# cc2652rb_v3.net
KiCad netlist of a schematic drawn in EAGLE
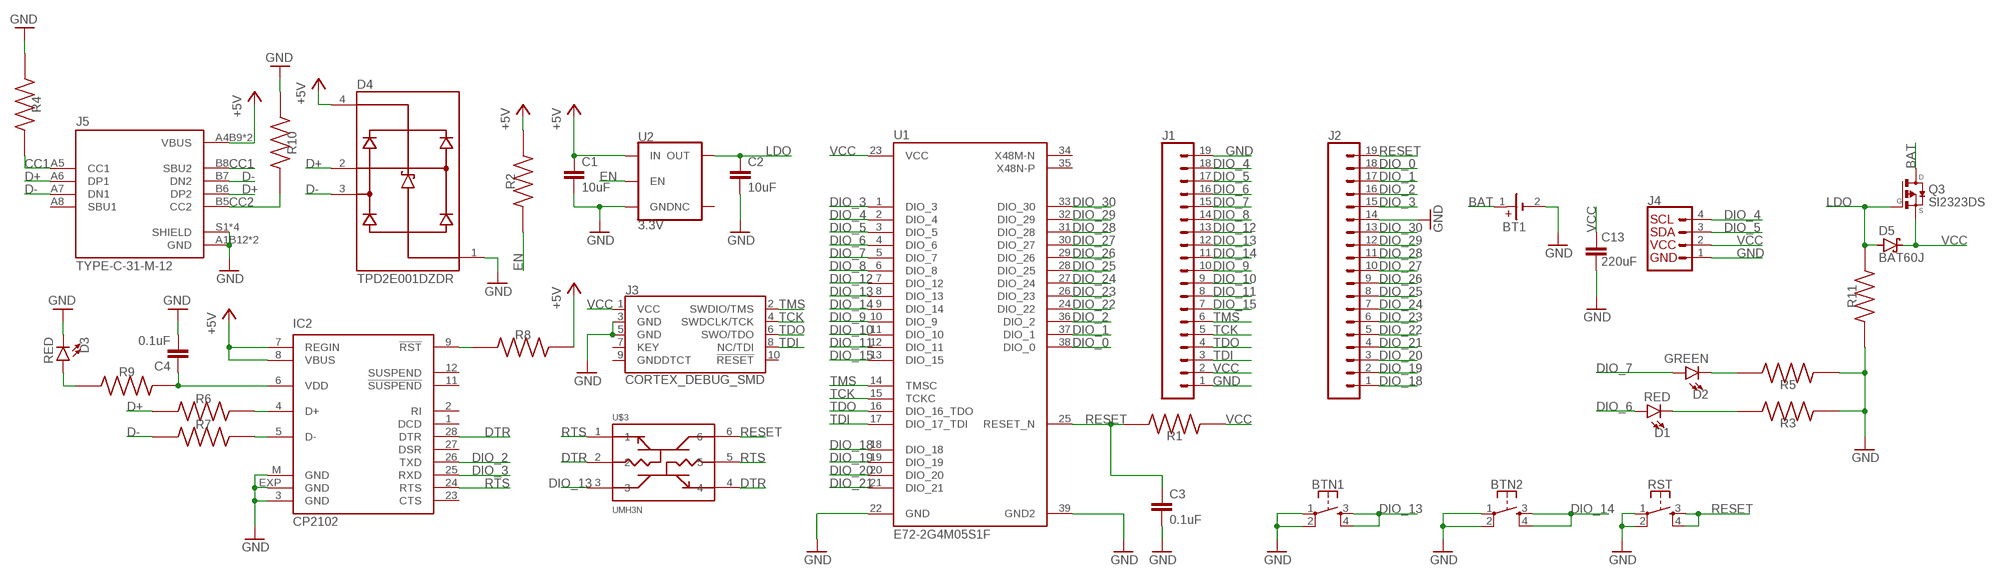
[diagram p0: schematic, sheet 1]

(export (version "E")
  (design (tool "Eeschema 10.0.6"))
  (components
    (comp (ref "BT1")
      (value "79527141")
      (footprint "eagle-import:79527141")
      (fields
        (field (name "DIGIKEY_PART_NO") "732-12325-2-ND")
        (field (name "MANUFACTURER") "Wurth Electronics Inc.")
        (field (name "CREATED_BY") "PCBLayout.com")
      )
      (libsource (lib "eagle-import") (part "79527141"))
    )
    (comp (ref "BTN1")
      (value "MOMENTARY-SWITCH-SPST-2-SMD-4.6X2.8MM")
      (footprint "eagle-import:TACTILE_SWITCH_SMD_4.6X2.8MM")
      (libsource (lib "eagle-import") (part "MOMENTARY-SWITCH-SPST-2-SMD-4.6X2.8MM"))
    )
    (comp (ref "BTN2")
      (value "MOMENTARY-SWITCH-SPST-2-SMD-4.6X2.8MM")
      (footprint "eagle-import:TACTILE_SWITCH_SMD_4.6X2.8MM")
      (libsource (lib "eagle-import") (part "MOMENTARY-SWITCH-SPST-2-SMD-4.6X2.8MM"))
    )
    (comp (ref "C1")
      (value "10uF")
      (footprint "eagle-import:0603")
      (libsource (lib "eagle-import") (part "10UF-0603-6.3V-20%"))
    )
    (comp (ref "C2")
      (value "10uF")
      (footprint "eagle-import:0603")
      (libsource (lib "eagle-import") (part "10UF-0603-6.3V-20%"))
    )
    (comp (ref "C3")
      (value "0.1uF")
      (footprint "eagle-import:0603")
      (libsource (lib "eagle-import") (part "0.1UF-0603-25V-(+80/-20%)"))
    )
    (comp (ref "C4")
      (value "0.1uF")
      (footprint "eagle-import:0603")
      (libsource (lib "eagle-import") (part "0.1UF-0603-25V-(+80/-20%)"))
    )
    (comp (ref "C13")
      (value "220uF")
      (footprint "eagle-import:CAPM7343X310")
      (libsource (lib "eagle-import") (part "CTANTALUM-2917(7343-METRIC)_"))
    )
    (comp (ref "D1")
      (value "RED")
      (footprint "eagle-import:LED-0603")
      (libsource (lib "eagle-import") (part "LED-RED0603"))
    )
    (comp (ref "D2")
      (value "GREEN")
      (footprint "eagle-import:LED-0603")
      (libsource (lib "eagle-import") (part "LED-GREEN0603"))
    )
    (comp (ref "D3")
      (value "RED")
      (footprint "eagle-import:LED-0603")
      (libsource (lib "eagle-import") (part "LED-RED0603"))
    )
    (comp (ref "D4")
      (value "TPD2E001DZDR")
      (footprint "eagle-import:SOT192P237X122-4N")
      (fields (field (name "MF") "Texas Instruments"))
      (libsource (lib "eagle-import") (part "TPD2E001DZDR"))
    )
    (comp (ref "D5")
      (value "BAT60J")
      (footprint "eagle-import:SOD323_ST")
      (libsource (lib "eagle-import") (part "BAT60J"))
    )
    (comp (ref "IC2")
      (value "CP2102")
      (footprint "eagle-import:MLP28")
      (fields (field (name "MF") "FARNELL") (field (name "MPN") "CP2102-GM"))
      (libsource (lib "eagle-import") (part "CP2102"))
    )
    (comp (ref "J1")
      (value "CONN_191X19_NO_SILK")
      (footprint "eagle-import:1X19_NO_SILK")
      (libsource (lib "eagle-import") (part "CONN_191X19_NO_SILK"))
    )
    (comp (ref "J2")
      (value "CONN_191X19_NO_SILK")
      (footprint "eagle-import:1X19_NO_SILK")
      (libsource (lib "eagle-import") (part "CONN_191X19_NO_SILK"))
    )
    (comp (ref "J3")
      (value "CORTEX_DEBUG_SMD")
      (footprint "eagle-import:SAMTECH_FTSH-105-01")
      (libsource (lib "eagle-import") (part "CORTEX_DEBUG_SMD"))
    )
    (comp (ref "J4")
      (value "QWIIC_CONNECTORJS-1MM")
      (footprint "eagle-import:1X04_1MM_RA")
      (libsource (lib "eagle-import") (part "QWIIC_CONNECTORJS-1MM"))
    )
    (comp (ref "J5")
      (value "TYPE-C-31-M-12")
      (footprint "eagle-import:HRO_TYPE-C-31-M-12")
      (fields (field (name "MF") "HRO Electronics Co., Ltd."))
      (libsource (lib "eagle-import") (part "TYPE-C-31-M-12"))
    )
    (comp (ref "Q3")
      (value "SI2323DS")
      (footprint "eagle-import:SOT23")
      (fields (field (name "MF") "Vishay Siliconix"))
      (libsource (lib "eagle-import") (part "SI2323DS"))
    )
    (comp (ref "R1")
      (value "100k")
      (footprint "eagle-import:RESC1005X40N")
      (fields (field (name "MF") "Yageo") (field (name "MP") "RC0402FR-073M6L"))
      (libsource (lib "eagle-import") (part "RC0402FR-073M6L"))
    )
    (comp (ref "R2")
      (value "10k")
      (footprint "eagle-import:RESC1005X40N")
      (fields (field (name "MF") "Yageo") (field (name "MP") "RC0402FR-073M6L"))
      (libsource (lib "eagle-import") (part "RC0402FR-073M6L"))
    )
    (comp (ref "R3")
      (value "2k")
      (footprint "eagle-import:RESC1005X40N")
      (fields (field (name "MF") "Yageo") (field (name "MP") "RC0402FR-073M6L"))
      (libsource (lib "eagle-import") (part "RC0402FR-073M6L"))
    )
    (comp (ref "R4")
      (value "5.1k")
      (footprint "eagle-import:RESC1005X40N")
      (fields (field (name "MF") "Yageo") (field (name "MP") "RC0402FR-073M6L"))
      (libsource (lib "eagle-import") (part "RC0402FR-073M6L"))
    )
    (comp (ref "R5")
      (value "2k")
      (footprint "eagle-import:RESC1005X40N")
      (fields (field (name "MF") "Yageo") (field (name "MP") "RC0402FR-073M6L"))
      (libsource (lib "eagle-import") (part "RC0402FR-073M6L"))
    )
    (comp (ref "R6")
      (value "33Ohm")
      (footprint "eagle-import:RESC1005X40N")
      (fields (field (name "MF") "Yageo") (field (name "MP") "RC0402FR-073M6L"))
      (libsource (lib "eagle-import") (part "RC0402FR-073M6L"))
    )
    (comp (ref "R7")
      (value "33Ohm")
      (footprint "eagle-import:RESC1005X40N")
      (fields (field (name "MF") "Yageo") (field (name "MP") "RC0402FR-073M6L"))
      (libsource (lib "eagle-import") (part "RC0402FR-073M6L"))
    )
    (comp (ref "R8")
      (value "10k")
      (footprint "eagle-import:RESC1005X40N")
      (fields (field (name "MF") "Yageo") (field (name "MP") "RC0402FR-073M6L"))
      (libsource (lib "eagle-import") (part "RC0402FR-073M6L"))
    )
    (comp (ref "R9")
      (value "RC0402FR-073M6L")
      (footprint "eagle-import:RESC1005X40N")
      (fields (field (name "MF") "Yageo"))
      (libsource (lib "eagle-import") (part "RC0402FR-073M6L"))
    )
    (comp (ref "R10")
      (value "5.1k")
      (footprint "eagle-import:RESC1005X40N")
      (fields (field (name "MF") "Yageo") (field (name "MP") "RC0402FR-073M6L"))
      (libsource (lib "eagle-import") (part "RC0402FR-073M6L"))
    )
    (comp (ref "R11")
      (value "10k")
      (footprint "eagle-import:RESC1005X40N")
      (fields (field (name "MF") "Yageo") (field (name "MP") "RC0402FR-073M6L"))
      (libsource (lib "eagle-import") (part "RC0402FR-073M6L"))
    )
    (comp (ref "RST")
      (value "MOMENTARY-SWITCH-SPST-2-SMD-4.6X2.8MM")
      (footprint "eagle-import:TACTILE_SWITCH_SMD_4.6X2.8MM")
      (libsource (lib "eagle-import") (part "MOMENTARY-SWITCH-SPST-2-SMD-4.6X2.8MM"))
    )
    (comp (ref "U$3")
      (value "UMH3N")
      (footprint "eagle-import:SOP65P210X100-6N")
      (fields (field (name "MF") "Rohm"))
      (libsource (lib "eagle-import") (part "UMH3N"))
    )
    (comp (ref "U1")
      (value "E72-2G4M05S1F")
      (footprint "eagle-import:E72-2G4M05S1F")
      (libsource (lib "eagle-import") (part "E72-2G4M05S1F"))
    )
    (comp (ref "U2")
      (value "3.3V")
      (footprint "eagle-import:SOT23-5")
      (libsource (lib "eagle-import") (part "V_REG_AP2112K-3.3V"))
    )
  )
  (nets
    (net (code "1") (name "+5V") (class "Default")
      (node (ref "C1") (pin "1") (pinfunction "1_1") (pintype "passive"))
      (node (ref "D4") (pin "4") (pinfunction "VCC_4") (pintype "power_in"))
      (node (ref "IC2") (pin "7") (pinfunction "REGIN_7") (pintype "passive"))
      (node (ref "IC2") (pin "8") (pinfunction "VBUS_8") (pintype "input"))
      (node (ref "J5") (pin "A4B9") (pinfunction "VBUS_A4B9") (pintype "power_in"))
      (node (ref "J5") (pin "B4A9") (pinfunction "VBUS_B4A9") (pintype "power_in"))
      (node (ref "R2") (pin "2") (pinfunction "2_2") (pintype "passive"))
      (node (ref "R8") (pin "2") (pinfunction "2_2") (pintype "passive"))
      (node (ref "U2") (pin "1") (pinfunction "IN_1") (pintype "input"))
    )
    (net (code "2") (name "/BAT") (class "Default")
      (node (ref "BT1") (pin "1") (pinfunction "+_1") (pintype "passive"))
      (node (ref "Q3") (pin "3") (pinfunction "D_3") (pintype "passive"))
    )
    (net (code "3") (name "/CC1") (class "Default")
      (node (ref "J5") (pin "A5") (pinfunction "CC1_A5") (pintype "bidirectional"))
      (node (ref "J5") (pin "B8") (pinfunction "SBU2_B8") (pintype "bidirectional"))
      (node (ref "R4") (pin "2") (pinfunction "2_2") (pintype "passive"))
    )
    (net (code "4") (name "/CC2") (class "Default")
      (node (ref "J5") (pin "B5") (pinfunction "CC2_B5") (pintype "bidirectional"))
      (node (ref "R10") (pin "2") (pinfunction "2_2") (pintype "passive"))
    )
    (net (code "5") (name "/D+") (class "Default")
      (node (ref "D4") (pin "2") (pinfunction "IO1_2") (pintype "bidirectional"))
      (node (ref "J5") (pin "A6") (pinfunction "DP1_A6") (pintype "bidirectional"))
      (node (ref "J5") (pin "B6") (pinfunction "DP2_B6") (pintype "bidirectional"))
      (node (ref "R6") (pin "1") (pinfunction "1_1") (pintype "passive"))
    )
    (net (code "6") (name "/D-") (class "Default")
      (node (ref "D4") (pin "3") (pinfunction "IO2_3") (pintype "bidirectional"))
      (node (ref "J5") (pin "A7") (pinfunction "DN1_A7") (pintype "bidirectional"))
      (node (ref "J5") (pin "B7") (pinfunction "DN2_B7") (pintype "bidirectional"))
      (node (ref "R7") (pin "1") (pinfunction "1_1") (pintype "passive"))
    )
    (net (code "7") (name "/DIO_0") (class "Default")
      (node (ref "J2") (pin "18") (pinfunction "18_18") (pintype "passive"))
      (node (ref "U1") (pin "38") (pinfunction "DIO_0_38") (pintype "bidirectional"))
    )
    (net (code "8") (name "/DIO_1") (class "Default")
      (node (ref "J2") (pin "17") (pinfunction "17_17") (pintype "passive"))
      (node (ref "U1") (pin "37") (pinfunction "DIO_1_37") (pintype "bidirectional"))
    )
    (net (code "9") (name "/DIO_2") (class "Default")
      (node (ref "IC2") (pin "26") (pinfunction "TXD_26") (pintype "output"))
      (node (ref "J2") (pin "16") (pinfunction "16_16") (pintype "passive"))
      (node (ref "U1") (pin "36") (pinfunction "DIO_2_36") (pintype "bidirectional"))
    )
    (net (code "10") (name "/DIO_3") (class "Default")
      (node (ref "IC2") (pin "25") (pinfunction "RXD_25") (pintype "input"))
      (node (ref "J2") (pin "15") (pinfunction "15_15") (pintype "passive"))
      (node (ref "U1") (pin "1") (pinfunction "DIO_3_1") (pintype "bidirectional"))
    )
    (net (code "11") (name "/DIO_4") (class "Default")
      (node (ref "J1") (pin "18") (pinfunction "18_18") (pintype "passive"))
      (node (ref "J4") (pin "4") (pinfunction "SCL_4") (pintype "passive"))
      (node (ref "U1") (pin "2") (pinfunction "DIO_4_2") (pintype "bidirectional"))
    )
    (net (code "12") (name "/DIO_5") (class "Default")
      (node (ref "J1") (pin "17") (pinfunction "17_17") (pintype "passive"))
      (node (ref "J4") (pin "3") (pinfunction "SDA_3") (pintype "passive"))
      (node (ref "U1") (pin "3") (pinfunction "DIO_5_3") (pintype "bidirectional"))
    )
    (net (code "13") (name "/DIO_6") (class "Default")
      (node (ref "D1") (pin "A") (pinfunction "A_A") (pintype "passive"))
      (node (ref "J1") (pin "16") (pinfunction "16_16") (pintype "passive"))
      (node (ref "U1") (pin "4") (pinfunction "DIO_6_4") (pintype "bidirectional"))
    )
    (net (code "14") (name "/DIO_7") (class "Default")
      (node (ref "D2") (pin "A") (pinfunction "A_A") (pintype "passive"))
      (node (ref "J1") (pin "15") (pinfunction "15_15") (pintype "passive"))
      (node (ref "U1") (pin "5") (pinfunction "DIO_7_5") (pintype "bidirectional"))
    )
    (net (code "15") (name "/DIO_8") (class "Default")
      (node (ref "J1") (pin "14") (pinfunction "14_14") (pintype "passive"))
      (node (ref "U1") (pin "6") (pinfunction "DIO_8_6") (pintype "bidirectional"))
    )
    (net (code "16") (name "/DIO_9") (class "Default")
      (node (ref "J1") (pin "10") (pinfunction "10_10") (pintype "passive"))
      (node (ref "U1") (pin "10") (pinfunction "DIO_9_10") (pintype "bidirectional"))
    )
    (net (code "17") (name "/DIO_10") (class "Default")
      (node (ref "J1") (pin "9") (pinfunction "9_9") (pintype "passive"))
      (node (ref "U1") (pin "11") (pinfunction "DIO_10_11") (pintype "bidirectional"))
    )
    (net (code "18") (name "/DIO_11") (class "Default")
      (node (ref "J1") (pin "8") (pinfunction "8_8") (pintype "passive"))
      (node (ref "U1") (pin "12") (pinfunction "DIO_11_12") (pintype "bidirectional"))
    )
    (net (code "19") (name "/DIO_12") (class "Default")
      (node (ref "J1") (pin "13") (pinfunction "13_13") (pintype "passive"))
      (node (ref "U1") (pin "7") (pinfunction "DIO_12_7") (pintype "bidirectional"))
    )
    (net (code "20") (name "/DIO_13") (class "Default")
      (node (ref "BTN1") (pin "3") (pinfunction "3_3") (pintype "passive"))
      (node (ref "BTN1") (pin "4") (pinfunction "4_4") (pintype "passive"))
      (node (ref "J1") (pin "12") (pinfunction "12_12") (pintype "passive"))
      (node (ref "U$3") (pin "3") (pinfunction "3_3") (pintype "bidirectional"))
      (node (ref "U1") (pin "8") (pinfunction "DIO_13_8") (pintype "bidirectional"))
    )
    (net (code "21") (name "/DIO_14") (class "Default")
      (node (ref "BTN2") (pin "3") (pinfunction "3_3") (pintype "passive"))
      (node (ref "BTN2") (pin "4") (pinfunction "4_4") (pintype "passive"))
      (node (ref "J1") (pin "11") (pinfunction "11_11") (pintype "passive"))
      (node (ref "U1") (pin "9") (pinfunction "DIO_14_9") (pintype "bidirectional"))
    )
    (net (code "22") (name "/DIO_15") (class "Default")
      (node (ref "J1") (pin "7") (pinfunction "7_7") (pintype "passive"))
      (node (ref "U1") (pin "13") (pinfunction "DIO_15_13") (pintype "bidirectional"))
    )
    (net (code "23") (name "/DIO_18") (class "Default")
      (node (ref "J2") (pin "1") (pinfunction "1_1") (pintype "passive"))
      (node (ref "U1") (pin "18") (pinfunction "DIO_18_18") (pintype "bidirectional"))
    )
    (net (code "24") (name "/DIO_19") (class "Default")
      (node (ref "J2") (pin "2") (pinfunction "2_2") (pintype "passive"))
      (node (ref "U1") (pin "19") (pinfunction "DIO_19_19") (pintype "bidirectional"))
    )
    (net (code "25") (name "/DIO_20") (class "Default")
      (node (ref "J2") (pin "3") (pinfunction "3_3") (pintype "passive"))
      (node (ref "U1") (pin "20") (pinfunction "DIO_20_20") (pintype "bidirectional"))
    )
    (net (code "26") (name "/DIO_21") (class "Default")
      (node (ref "J2") (pin "4") (pinfunction "4_4") (pintype "passive"))
      (node (ref "U1") (pin "21") (pinfunction "DIO_21_21") (pintype "bidirectional"))
    )
    (net (code "27") (name "/DIO_22") (class "Default")
      (node (ref "J2") (pin "5") (pinfunction "5_5") (pintype "passive"))
      (node (ref "U1") (pin "24") (pinfunction "DIO_22_24") (pintype "bidirectional"))
    )
    (net (code "28") (name "/DIO_23") (class "Default")
      (node (ref "J2") (pin "6") (pinfunction "6_6") (pintype "passive"))
      (node (ref "U1") (pin "26") (pinfunction "DIO_23_26") (pintype "bidirectional"))
    )
    (net (code "29") (name "/DIO_24") (class "Default")
      (node (ref "J2") (pin "7") (pinfunction "7_7") (pintype "passive"))
      (node (ref "U1") (pin "27") (pinfunction "DIO_24_27") (pintype "bidirectional"))
    )
    (net (code "30") (name "/DIO_25") (class "Default")
      (node (ref "J2") (pin "8") (pinfunction "8_8") (pintype "passive"))
      (node (ref "U1") (pin "28") (pinfunction "DIO_25_28") (pintype "bidirectional"))
    )
    (net (code "31") (name "/DIO_26") (class "Default")
      (node (ref "J2") (pin "9") (pinfunction "9_9") (pintype "passive"))
      (node (ref "U1") (pin "29") (pinfunction "DIO_26_29") (pintype "bidirectional"))
    )
    (net (code "32") (name "/DIO_27") (class "Default")
      (node (ref "J2") (pin "10") (pinfunction "10_10") (pintype "passive"))
      (node (ref "U1") (pin "30") (pinfunction "DIO_27_30") (pintype "bidirectional"))
    )
    (net (code "33") (name "/DIO_28") (class "Default")
      (node (ref "J2") (pin "11") (pinfunction "11_11") (pintype "passive"))
      (node (ref "U1") (pin "31") (pinfunction "DIO_28_31") (pintype "bidirectional"))
    )
    (net (code "34") (name "/DIO_29") (class "Default")
      (node (ref "J2") (pin "12") (pinfunction "12_12") (pintype "passive"))
      (node (ref "U1") (pin "32") (pinfunction "DIO_29_32") (pintype "bidirectional"))
    )
    (net (code "35") (name "/DIO_30") (class "Default")
      (node (ref "J2") (pin "13") (pinfunction "13_13") (pintype "passive"))
      (node (ref "U1") (pin "33") (pinfunction "DIO_30_33") (pintype "bidirectional"))
    )
    (net (code "36") (name "/DTR") (class "Default")
      (node (ref "IC2") (pin "28") (pinfunction "DTR_28") (pintype "output"))
      (node (ref "U$3") (pin "2") (pinfunction "2_2") (pintype "bidirectional"))
      (node (ref "U$3") (pin "4") (pinfunction "4_4") (pintype "bidirectional"))
    )
    (net (code "37") (name "/EN") (class "Default")
      (node (ref "R2") (pin "1") (pinfunction "1_1") (pintype "passive"))
      (node (ref "U2") (pin "3") (pinfunction "EN_3") (pintype "input"))
    )
    (net (code "38") (name "/LDO") (class "Default")
      (node (ref "C2") (pin "1") (pinfunction "1_1") (pintype "passive"))
      (node (ref "D5") (pin "A") (pinfunction "A_A") (pintype "passive"))
      (node (ref "Q3") (pin "1") (pinfunction "G_1") (pintype "passive"))
      (node (ref "R11") (pin "2") (pinfunction "2_2") (pintype "passive"))
      (node (ref "U2") (pin "5") (pinfunction "OUT_5") (pintype "passive"))
    )
    (net (code "39") (name "/RESET") (class "Default")
      (node (ref "C3") (pin "1") (pinfunction "1_1") (pintype "passive"))
      (node (ref "J2") (pin "19") (pinfunction "19_19") (pintype "passive"))
      (node (ref "R1") (pin "2") (pinfunction "2_2") (pintype "passive"))
      (node (ref "RST") (pin "3") (pinfunction "3_3") (pintype "passive"))
      (node (ref "RST") (pin "4") (pinfunction "4_4") (pintype "passive"))
      (node (ref "U$3") (pin "6") (pinfunction "6_6") (pintype "bidirectional"))
      (node (ref "U1") (pin "25") (pinfunction "RESET_N_25") (pintype "bidirectional"))
    )
    (net (code "40") (name "/RTS") (class "Default")
      (node (ref "IC2") (pin "24") (pinfunction "RTS_24") (pintype "output"))
      (node (ref "U$3") (pin "1") (pinfunction "1_1") (pintype "bidirectional"))
      (node (ref "U$3") (pin "5") (pinfunction "5_5") (pintype "bidirectional"))
    )
    (net (code "41") (name "/TCK") (class "Default")
      (node (ref "J1") (pin "5") (pinfunction "5_5") (pintype "passive"))
      (node (ref "J3") (pin "4") (pinfunction "SWDCLK/TCK_4") (pintype "bidirectional"))
      (node (ref "U1") (pin "15") (pinfunction "TCKC_15") (pintype "bidirectional"))
    )
    (net (code "42") (name "/TDI") (class "Default")
      (node (ref "J1") (pin "3") (pinfunction "3_3") (pintype "passive"))
      (node (ref "J3") (pin "8") (pinfunction "NC/TDI_8") (pintype "bidirectional"))
      (node (ref "U1") (pin "17") (pinfunction "DIO_17_TDI_17") (pintype "bidirectional"))
    )
    (net (code "43") (name "/TDO") (class "Default")
      (node (ref "J1") (pin "4") (pinfunction "4_4") (pintype "passive"))
      (node (ref "J3") (pin "6") (pinfunction "SWO/TDO_6") (pintype "bidirectional"))
      (node (ref "U1") (pin "16") (pinfunction "DIO_16_TDO_16") (pintype "bidirectional"))
    )
    (net (code "44") (name "/TMS") (class "Default")
      (node (ref "J1") (pin "6") (pinfunction "6_6") (pintype "passive"))
      (node (ref "J3") (pin "2") (pinfunction "SWDIO/TMS_2") (pintype "bidirectional"))
      (node (ref "U1") (pin "14") (pinfunction "TMSC_14") (pintype "bidirectional"))
    )
    (net (code "45") (name "/VCC") (class "Default")
      (node (ref "C13") (pin "1") (pinfunction "1_1") (pintype "passive"))
      (node (ref "D5") (pin "C") (pinfunction "C_C") (pintype "passive"))
      (node (ref "J1") (pin "2") (pinfunction "2_2") (pintype "passive"))
      (node (ref "J3") (pin "1") (pinfunction "VCC_1") (pintype "bidirectional"))
      (node (ref "J4") (pin "2") (pinfunction "VCC_2") (pintype "power_in"))
      (node (ref "Q3") (pin "2") (pinfunction "S_2") (pintype "passive"))
      (node (ref "R1") (pin "1") (pinfunction "1_1") (pintype "passive"))
      (node (ref "U1") (pin "23") (pinfunction "VCC_23") (pintype "bidirectional"))
    )
    (net (code "46") (name "GND") (class "Default")
      (node (ref "BT1") (pin "2") (pinfunction "-_2") (pintype "passive"))
      (node (ref "BTN1") (pin "1") (pinfunction "1_1") (pintype "passive"))
      (node (ref "BTN1") (pin "2") (pinfunction "2_2") (pintype "passive"))
      (node (ref "BTN2") (pin "1") (pinfunction "1_1") (pintype "passive"))
      (node (ref "BTN2") (pin "2") (pinfunction "2_2") (pintype "passive"))
      (node (ref "C1") (pin "2") (pinfunction "2_2") (pintype "passive"))
      (node (ref "C13") (pin "2") (pinfunction "2_2") (pintype "passive"))
      (node (ref "C2") (pin "2") (pinfunction "2_2") (pintype "passive"))
      (node (ref "C3") (pin "2") (pinfunction "2_2") (pintype "passive"))
      (node (ref "C4") (pin "2") (pinfunction "2_2") (pintype "passive"))
      (node (ref "D3") (pin "C") (pinfunction "C_C") (pintype "passive"))
      (node (ref "D4") (pin "1") (pinfunction "GND_1") (pintype "power_in"))
      (node (ref "IC2") (pin "3") (pinfunction "GND_3") (pintype "power_in"))
      (node (ref "IC2") (pin "EXP") (pinfunction "GND_EXP") (pintype "power_in"))
      (node (ref "IC2") (pin "M") (pinfunction "GND_M") (pintype "power_in"))
      (node (ref "J1") (pin "1") (pinfunction "1_1") (pintype "passive"))
      (node (ref "J1") (pin "19") (pinfunction "19_19") (pintype "passive"))
      (node (ref "J2") (pin "14") (pinfunction "14_14") (pintype "passive"))
      (node (ref "J3") (pin "3") (pinfunction "GND_3") (pintype "bidirectional"))
      (node (ref "J3") (pin "5") (pinfunction "GND_5") (pintype "bidirectional"))
      (node (ref "J4") (pin "1") (pinfunction "GND_1") (pintype "power_in"))
      (node (ref "J5") (pin "A1B12") (pinfunction "GND_A1B12") (pintype "power_in"))
      (node (ref "J5") (pin "B1A12") (pinfunction "GND_B1A12") (pintype "power_in"))
      (node (ref "J5") (pin "S1") (pinfunction "SHIELD_S1") (pintype "passive"))
      (node (ref "J5") (pin "S2") (pinfunction "SHIELD_S2") (pintype "passive"))
      (node (ref "J5") (pin "S3") (pinfunction "SHIELD_S3") (pintype "passive"))
      (node (ref "J5") (pin "S4") (pinfunction "SHIELD_S4") (pintype "passive"))
      (node (ref "R10") (pin "1") (pinfunction "1_1") (pintype "passive"))
      (node (ref "R11") (pin "1") (pinfunction "1_1") (pintype "passive"))
      (node (ref "R3") (pin "1") (pinfunction "1_1") (pintype "passive"))
      (node (ref "R4") (pin "1") (pinfunction "1_1") (pintype "passive"))
      (node (ref "R5") (pin "1") (pinfunction "1_1") (pintype "passive"))
      (node (ref "RST") (pin "1") (pinfunction "1_1") (pintype "passive"))
      (node (ref "RST") (pin "2") (pinfunction "2_2") (pintype "passive"))
      (node (ref "U1") (pin "22") (pinfunction "GND_22") (pintype "bidirectional"))
      (node (ref "U1") (pin "39") (pinfunction "GND2_39") (pintype "bidirectional"))
      (node (ref "U2") (pin "2") (pinfunction "GND_2") (pintype "input"))
    )
    (net (code "47") (name "Net-(D1-PadC)") (class "Default")
      (node (ref "D1") (pin "C") (pinfunction "C_C") (pintype "passive"))
      (node (ref "R3") (pin "2") (pinfunction "2_2") (pintype "passive"))
    )
    (net (code "48") (name "Net-(D2-PadC)") (class "Default")
      (node (ref "D2") (pin "C") (pinfunction "C_C") (pintype "passive"))
      (node (ref "R5") (pin "2") (pinfunction "2_2") (pintype "passive"))
    )
    (net (code "49") (name "Net-(D3-PadA)") (class "Default")
      (node (ref "D3") (pin "A") (pinfunction "A_A") (pintype "passive"))
      (node (ref "R9") (pin "2") (pinfunction "2_2") (pintype "passive"))
    )
    (net (code "50") (name "Net-(IC2-D+)") (class "Default")
      (node (ref "IC2") (pin "4") (pinfunction "D+_4") (pintype "bidirectional"))
      (node (ref "R6") (pin "2") (pinfunction "2_2") (pintype "passive"))
    )
    (net (code "51") (name "Net-(IC2-D-)") (class "Default")
      (node (ref "IC2") (pin "5") (pinfunction "D-_5") (pintype "bidirectional"))
      (node (ref "R7") (pin "2") (pinfunction "2_2") (pintype "passive"))
    )
    (net (code "52") (name "Net-(IC2-VDD)") (class "Default")
      (node (ref "C4") (pin "1") (pinfunction "1_1") (pintype "passive"))
      (node (ref "IC2") (pin "6") (pinfunction "VDD_6") (pintype "power_in"))
      (node (ref "R9") (pin "1") (pinfunction "1_1") (pintype "passive"))
    )
    (net (code "53") (name "Net-(IC2-~{RST})") (class "Default")
      (node (ref "IC2") (pin "9") (pinfunction "~{RST}_9") (pintype "bidirectional"))
      (node (ref "R8") (pin "1") (pinfunction "1_1") (pintype "passive"))
    )
    (net (code "54") (name "unconnected-(IC2-CTS-Pad23)") (class "Default")
      (node (ref "IC2") (pin "23") (pinfunction "CTS_23") (pintype "input"))
    )
    (net (code "55") (name "unconnected-(IC2-DCD-Pad1)") (class "Default")
      (node (ref "IC2") (pin "1") (pinfunction "DCD_1") (pintype "input"))
    )
    (net (code "56") (name "unconnected-(IC2-DSR-Pad27)") (class "Default")
      (node (ref "IC2") (pin "27") (pinfunction "DSR_27") (pintype "input"))
    )
    (net (code "57") (name "unconnected-(IC2-RI-Pad2)") (class "Default")
      (node (ref "IC2") (pin "2") (pinfunction "RI_2") (pintype "input"))
    )
    (net (code "58") (name "unconnected-(IC2-SUSPEND-Pad12)") (class "Default")
      (node (ref "IC2") (pin "12") (pinfunction "SUSPEND_12") (pintype "output"))
    )
    (net (code "59") (name "unconnected-(IC2-~{SUSPEND}-Pad11)") (class "Default")
      (node (ref "IC2") (pin "11") (pinfunction "~{SUSPEND}_11") (pintype "output"))
    )
    (net (code "60") (name "unconnected-(J3-GNDDTCT-Pad9)") (class "Default")
      (node (ref "J3") (pin "9") (pinfunction "GNDDTCT_9") (pintype "bidirectional"))
    )
    (net (code "61") (name "unconnected-(J3-KEY-Pad7)") (class "Default")
      (node (ref "J3") (pin "7") (pinfunction "KEY_7") (pintype "bidirectional"))
    )
    (net (code "62") (name "unconnected-(J3-~{RESET}-Pad10)") (class "Default")
      (node (ref "J3") (pin "10") (pinfunction "~{RESET}_10") (pintype "bidirectional"))
    )
    (net (code "63") (name "unconnected-(J5-SBU1-PadA8)") (class "Default")
      (node (ref "J5") (pin "A8") (pinfunction "SBU1_A8") (pintype "bidirectional"))
    )
    (net (code "64") (name "unconnected-(U1-X48M-N-Pad34)") (class "Default")
      (node (ref "U1") (pin "34") (pinfunction "X48M-N_34") (pintype "bidirectional"))
    )
    (net (code "65") (name "unconnected-(U1-X48N-P-Pad35)") (class "Default")
      (node (ref "U1") (pin "35") (pinfunction "X48N-P_35") (pintype "bidirectional"))
    )
    (net (code "66") (name "unconnected-(U2-NC-Pad4)") (class "Default")
      (node (ref "U2") (pin "4") (pinfunction "NC_4") (pintype "no_connect"))
    )
  )
)
